# LCmeter0-LCD-8pinlcd-PIC_COMP.net
KiCad netlist of a schematic drawn in EAGLE
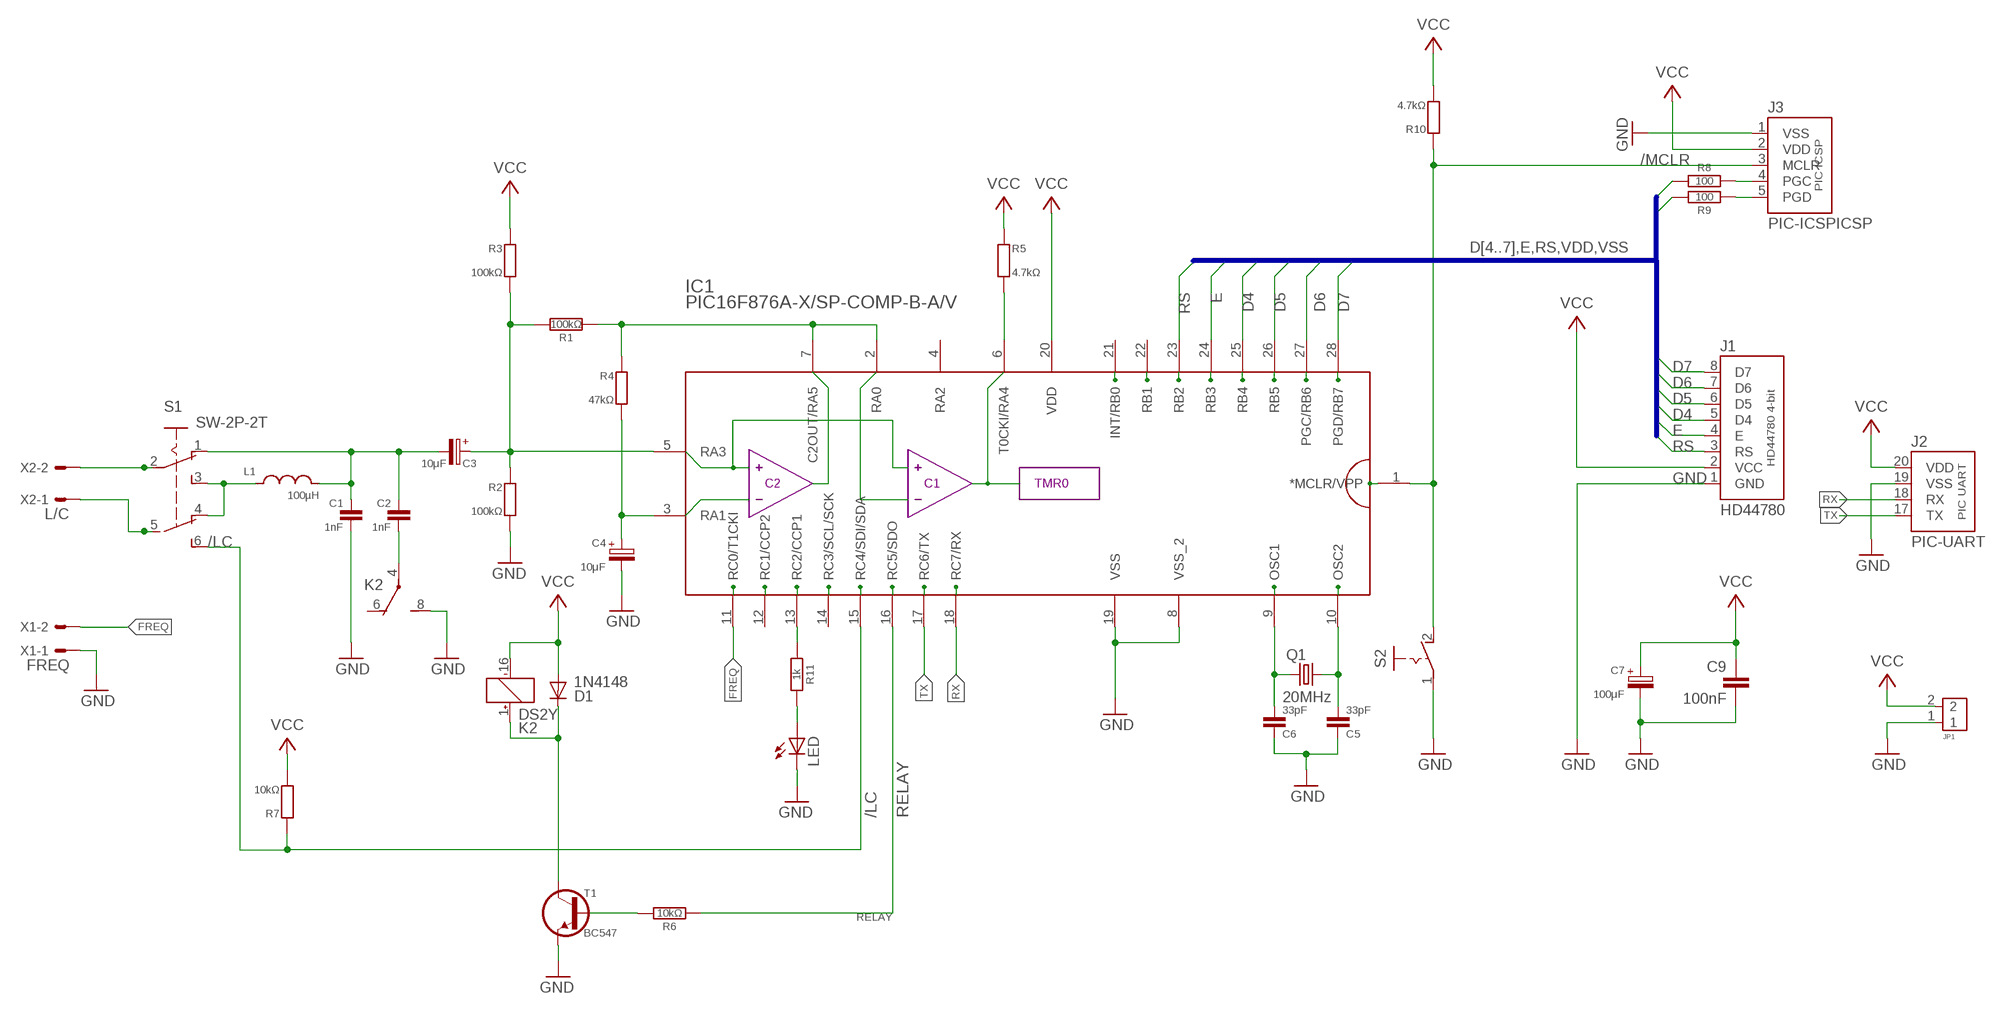
[diagram p0: schematic, sheet 1]

(export (version "E")
  (design (tool "Eeschema 10.0.6"))
  (components
    (comp (ref "C1")
      (value "1nF")
      (footprint "eagle-import:C050-020X036")
      (libsource (lib "eagle-import") (part "C050-020X036"))
    )
    (comp (ref "C2")
      (value "1nF")
      (footprint "eagle-import:C050-020X036")
      (libsource (lib "eagle-import") (part "C050-020X036"))
    )
    (comp (ref "C3")
      (value "10μF")
      (footprint "eagle-import:E2,5-4")
      (libsource (lib "eagle-import") (part "CPOL-HE2,5-4"))
    )
    (comp (ref "C4")
      (value "10μF")
      (footprint "eagle-import:E2,5-4")
      (libsource (lib "eagle-import") (part "CPOLE2,5-4"))
    )
    (comp (ref "C5")
      (value "33pF")
      (footprint "eagle-import:C025-020X036")
      (libsource (lib "eagle-import") (part "C025-020X036"))
    )
    (comp (ref "C6")
      (value "33pF")
      (footprint "eagle-import:C025-020X036")
      (libsource (lib "eagle-import") (part "C025-020X036"))
    )
    (comp (ref "C7")
      (value "100μF")
      (footprint "eagle-import:E2,5-5")
      (libsource (lib "eagle-import") (part "CPOLE2.5-5"))
    )
    (comp (ref "C9")
      (value "100nF")
      (footprint "eagle-import:C025-024X044")
      (libsource (lib "eagle-import") (part "C-EU025-024X044"))
    )
    (comp (ref "D1")
      (value "1N4148")
      (footprint "eagle-import:DO34-7")
      (libsource (lib "eagle-import") (part "1N414834-7"))
    )
    (comp (ref "IC1")
      (value "PIC16F876A-X/SP-COMP-B-A/V")
      (footprint "eagle-import:DIL28-3_V")
      (libsource (lib "eagle-import") (part "PIC16F876A-X/SP-COMP-B-A/V"))
    )
    (comp (ref "J1")
      (value "HD44780")
      (footprint "eagle-import:CONN-8P")
      (libsource (lib "eagle-import") (part "HD44780-4BIT-8PIN"))
    )
    (comp (ref "J2")
      (value "PIC-UART")
      (footprint "eagle-import:PIC-UART")
      (libsource (lib "eagle-import") (part "PIC-UART"))
    )
    (comp (ref "J3")
      (value "PIC-ICSPICSP")
      (footprint "eagle-import:PIC-ICSP")
      (libsource (lib "eagle-import") (part "PIC-ICSPICSP"))
    )
    (comp (ref "JP1")
      (value "CONN-2P2P/V")
      (footprint "eagle-import:CONN-2P-V")
      (libsource (lib "eagle-import") (part "CONN-2P2P/V"))
    )
    (comp (ref "K2")
      (value "DS2Y")
      (footprint "eagle-import:DS2Y")
      (fields (field (name "MPN") "DS2Y-S-DC5V"))
      (libsource (lib "eagle-import") (part "DS2Y-S-DC5V"))
    )
    (comp (ref "L1")
      (value "100µH")
      (footprint "eagle-import:L-02_5V")
      (libsource (lib "eagle-import") (part "L-SHORT02/5"))
    )
    (comp (ref "LED")
      (value "TLLG4400")
      (footprint "eagle-import:LED3MM")
      (fields (field (name "MF") "VISHAY SEMICONDUCTOR"))
      (libsource (lib "eagle-import") (part "TLLG4400"))
    )
    (comp (ref "Q1")
      (value "20MHz")
      (footprint "eagle-import:HC49")
      (libsource (lib "eagle-import") (part "CRYSTALHC49"))
    )
    (comp (ref "R1")
      (value "100kΩ")
      (footprint "eagle-import:0202_7")
      (libsource (lib "eagle-import") (part "R-H0202/7"))
    )
    (comp (ref "R2")
      (value "100kΩ")
      (footprint "eagle-import:0202_7")
      (libsource (lib "eagle-import") (part "R0202/7"))
    )
    (comp (ref "R3")
      (value "100kΩ")
      (footprint "eagle-import:0202_7")
      (libsource (lib "eagle-import") (part "R0202/7"))
    )
    (comp (ref "R4")
      (value "47kΩ")
      (footprint "eagle-import:0202_7")
      (libsource (lib "eagle-import") (part "R0202/7"))
    )
    (comp (ref "R5")
      (value "4.7kΩ")
      (footprint "eagle-import:0202_7")
      (libsource (lib "eagle-import") (part "R0202/7"))
    )
    (comp (ref "R6")
      (value "10kΩ")
      (footprint "eagle-import:0202_7")
      (libsource (lib "eagle-import") (part "R-H0202/7"))
    )
    (comp (ref "R7")
      (value "10kΩ")
      (footprint "eagle-import:0202_10")
      (libsource (lib "eagle-import") (part "R0202/10"))
    )
    (comp (ref "R8")
      (value "100")
      (footprint "eagle-import:0202_5")
      (libsource (lib "eagle-import") (part "R-H0202/5"))
    )
    (comp (ref "R9")
      (value "100")
      (footprint "eagle-import:0202_5")
      (libsource (lib "eagle-import") (part "R-H0202/5"))
    )
    (comp (ref "R10")
      (value "4.7kΩ")
      (footprint "eagle-import:0202_7")
      (libsource (lib "eagle-import") (part "R0202/7"))
    )
    (comp (ref "R11")
      (value "1k")
      (footprint "eagle-import:0202_5")
      (libsource (lib "eagle-import") (part "R-H0202/5"))
    )
    (comp (ref "S1")
      (value "SW-2P-2T")
      (footprint "eagle-import:SLSW-2P2T")
      (libsource (lib "eagle-import") (part "SW-2P-2T"))
    )
    (comp (ref "S2")
      (value "PB-1P-1T")
      (footprint "eagle-import:PB-1P1T")
      (libsource (lib "eagle-import") (part "PB-1P-1T"))
    )
    (comp (ref "T1")
      (value "BC547")
      (footprint "eagle-import:TO92-CBE-A")
      (libsource (lib "eagle-import") (part "BC547CBE-A"))
    )
    (comp (ref "X1")
      (value "FREQ")
      (footprint "eagle-import:70543-02")
      (libsource (lib "eagle-import") (part "C-GRID-02-70543"))
    )
    (comp (ref "X2")
      (value "L/C")
      (footprint "eagle-import:70543-02")
      (libsource (lib "eagle-import") (part "C-GRID-02-70543"))
    )
  )
  (nets
    (net (code "3") (name "/D4") (class "Default")
      (node (ref "IC1") (pin "25") (pinfunction "RB4_25") (pintype "passive"))
      (node (ref "J1") (pin "5") (pinfunction "D4_5") (pintype "passive"))
    )
    (net (code "4") (name "/D5") (class "Default")
      (node (ref "IC1") (pin "26") (pinfunction "RB5_26") (pintype "passive"))
      (node (ref "J1") (pin "6") (pinfunction "D5_6") (pintype "passive"))
    )
    (net (code "5") (name "/D6") (class "Default")
      (node (ref "IC1") (pin "27") (pinfunction "PGC/RB6_27") (pintype "passive"))
      (node (ref "J1") (pin "7") (pinfunction "D6_7") (pintype "passive"))
      (node (ref "R9") (pin "1") (pinfunction "1_1") (pintype "passive"))
    )
    (net (code "6") (name "/D7") (class "Default")
      (node (ref "IC1") (pin "28") (pinfunction "PGD/RB7_28") (pintype "passive"))
      (node (ref "J1") (pin "8") (pinfunction "D7_8") (pintype "passive"))
      (node (ref "R8") (pin "1") (pinfunction "1_1") (pintype "passive"))
    )
    (net (code "7") (name "/E") (class "Default")
      (node (ref "IC1") (pin "24") (pinfunction "RB3_24") (pintype "passive"))
      (node (ref "J1") (pin "4") (pinfunction "E_4") (pintype "passive"))
    )
    (net (code "8") (name "/RELAY") (class "Default")
      (node (ref "IC1") (pin "16") (pinfunction "RC5/SDO_16") (pintype "passive"))
      (node (ref "R6") (pin "2") (pinfunction "2_2") (pintype "passive"))
    )
    (net (code "9") (name "/RS") (class "Default")
      (node (ref "IC1") (pin "23") (pinfunction "RB2_23") (pintype "passive"))
      (node (ref "J1") (pin "3") (pinfunction "RS_3") (pintype "passive"))
    )
    (net (code "11") (name "/{slash}LC") (class "Default")
      (node (ref "IC1") (pin "15") (pinfunction "RC4/SDI/SDA_15") (pintype "passive"))
      (node (ref "R7") (pin "1") (pinfunction "1_1") (pintype "passive"))
      (node (ref "S1") (pin "6") (pinfunction "S1_6") (pintype "passive"))
    )
    (net (code "12") (name "/{slash}MCLR") (class "Default")
      (node (ref "IC1") (pin "1") (pinfunction "*MCLR/VPP_1") (pintype "passive"))
      (node (ref "J3") (pin "3") (pinfunction "MCLR_3") (pintype "passive"))
      (node (ref "R10") (pin "1") (pinfunction "1_1") (pintype "passive"))
      (node (ref "S2") (pin "2") (pinfunction "S_2") (pintype "passive"))
    )
    (net (code "13") (name "FREQ") (class "Default")
      (node (ref "IC1") (pin "11") (pinfunction "RC0/T1CKI_11") (pintype "passive"))
      (node (ref "X1") (pin "2") (pinfunction "S_2") (pintype "passive"))
    )
    (net (code "14") (name "GND") (class "Default")
      (node (ref "C1") (pin "2") (pinfunction "2_2") (pintype "passive"))
      (node (ref "C4") (pin "-") (pinfunction "-_-") (pintype "passive"))
      (node (ref "C5") (pin "1") (pinfunction "1_1") (pintype "passive"))
      (node (ref "C6") (pin "1") (pinfunction "1_1") (pintype "passive"))
      (node (ref "C7") (pin "-") (pinfunction "-_-") (pintype "passive"))
      (node (ref "C9") (pin "2") (pinfunction "2_2") (pintype "passive"))
      (node (ref "IC1") (pin "19") (pinfunction "VSS_19") (pintype "passive"))
      (node (ref "IC1") (pin "8") (pinfunction "VSS_2_8") (pintype "passive"))
      (node (ref "J1") (pin "1") (pinfunction "GND_1") (pintype "passive"))
      (node (ref "J2") (pin "19") (pinfunction "VSS_19") (pintype "passive"))
      (node (ref "J3") (pin "1") (pinfunction "VSS_1") (pintype "passive"))
      (node (ref "JP1") (pin "1") (pinfunction "1_1") (pintype "bidirectional"))
      (node (ref "K2") (pin "8") (pinfunction "S_8") (pintype "passive"))
      (node (ref "LED") (pin "K") (pinfunction "C_K") (pintype "passive"))
      (node (ref "R2") (pin "2") (pinfunction "2_2") (pintype "passive"))
      (node (ref "S2") (pin "1") (pinfunction "P_1") (pintype "passive"))
      (node (ref "T1") (pin "E") (pinfunction "E_E") (pintype "passive"))
      (node (ref "X1") (pin "1") (pinfunction "S_1") (pintype "passive"))
    )
    (net (code "15") (name "Net-(IC1-C2OUT{slash}RA5)") (class "Default")
      (node (ref "IC1") (pin "2") (pinfunction "RA0_2") (pintype "passive"))
      (node (ref "IC1") (pin "7") (pinfunction "C2OUT/RA5_7") (pintype "passive"))
      (node (ref "R1") (pin "1") (pinfunction "1_1") (pintype "passive"))
      (node (ref "R4") (pin "1") (pinfunction "1_1") (pintype "passive"))
    )
    (net (code "16") (name "Net-(IC1-OSC1)") (class "Default")
      (node (ref "C6") (pin "2") (pinfunction "2_2") (pintype "passive"))
      (node (ref "IC1") (pin "9") (pinfunction "OSC1_9") (pintype "passive"))
      (node (ref "Q1") (pin "1") (pinfunction "1_1") (pintype "passive"))
    )
    (net (code "17") (name "Net-(IC1-OSC2)") (class "Default")
      (node (ref "C5") (pin "2") (pinfunction "2_2") (pintype "passive"))
      (node (ref "IC1") (pin "10") (pinfunction "OSC2_10") (pintype "passive"))
      (node (ref "Q1") (pin "2") (pinfunction "2_2") (pintype "passive"))
    )
    (net (code "18") (name "Net-(IC1-RA1)") (class "Default")
      (node (ref "C4") (pin "+") (pinfunction "+_+") (pintype "passive"))
      (node (ref "IC1") (pin "3") (pinfunction "RA1_3") (pintype "passive"))
      (node (ref "R4") (pin "2") (pinfunction "2_2") (pintype "passive"))
    )
    (net (code "19") (name "Net-(IC1-RA3)") (class "Default")
      (node (ref "C3") (pin "+") (pinfunction "+_+") (pintype "passive"))
      (node (ref "IC1") (pin "5") (pinfunction "RA3_5") (pintype "passive"))
      (node (ref "R1") (pin "2") (pinfunction "2_2") (pintype "passive"))
      (node (ref "R2") (pin "1") (pinfunction "1_1") (pintype "passive"))
      (node (ref "R3") (pin "2") (pinfunction "2_2") (pintype "passive"))
    )
    (net (code "20") (name "Net-(IC1-RC2{slash}CCP1)") (class "Default")
      (node (ref "IC1") (pin "13") (pinfunction "RC2/CCP1_13") (pintype "passive"))
      (node (ref "R11") (pin "2") (pinfunction "2_2") (pintype "passive"))
    )
    (net (code "21") (name "Net-(IC1-T0CKI{slash}RA4)") (class "Default")
      (node (ref "IC1") (pin "6") (pinfunction "T0CKI/RA4_6") (pintype "passive"))
      (node (ref "R5") (pin "2") (pinfunction "2_2") (pintype "passive"))
    )
    (net (code "22") (name "Net-(J3-PGC)") (class "Default")
      (node (ref "J3") (pin "4") (pinfunction "PGC_4") (pintype "passive"))
      (node (ref "R8") (pin "2") (pinfunction "2_2") (pintype "passive"))
    )
    (net (code "23") (name "Net-(J3-PGD)") (class "Default")
      (node (ref "J3") (pin "5") (pinfunction "PGD_5") (pintype "passive"))
      (node (ref "R9") (pin "2") (pinfunction "2_2") (pintype "passive"))
    )
    (net (code "24") (name "Net-(K2A-+)") (class "Default")
      (node (ref "D1") (pin "C") (pinfunction "C_C") (pintype "passive"))
      (node (ref "K2") (pin "1") (pinfunction "+_1") (pintype "passive"))
      (node (ref "T1") (pin "C") (pinfunction "C_C") (pintype "passive"))
    )
    (net (code "25") (name "Net-(K2B-P)") (class "Default")
      (node (ref "C2") (pin "2") (pinfunction "2_2") (pintype "passive"))
      (node (ref "K2") (pin "4") (pinfunction "P_4") (pintype "passive"))
    )
    (net (code "26") (name "Net-(LED-PadA)") (class "Default")
      (node (ref "LED") (pin "A") (pinfunction "A_A") (pintype "passive"))
      (node (ref "R11") (pin "1") (pinfunction "1_1") (pintype "passive"))
    )
    (net (code "27") (name "Net-(R6-Pad1)") (class "Default")
      (node (ref "R6") (pin "1") (pinfunction "1_1") (pintype "passive"))
      (node (ref "T1") (pin "B") (pinfunction "B_B") (pintype "passive"))
    )
    (net (code "28") (name "Net-(S1-O)") (class "Default")
      (node (ref "C1") (pin "1") (pinfunction "1_1") (pintype "passive"))
      (node (ref "C2") (pin "1") (pinfunction "1_1") (pintype "passive"))
      (node (ref "C3") (pin "-") (pinfunction "-_-") (pintype "passive"))
      (node (ref "L1") (pin "2") (pinfunction "2_2") (pintype "passive"))
      (node (ref "S1") (pin "1") (pinfunction "O_1") (pintype "passive"))
    )
    (net (code "29") (name "Net-(S1-O1)") (class "Default")
      (node (ref "L1") (pin "1") (pinfunction "1_1") (pintype "passive"))
      (node (ref "S1") (pin "3") (pinfunction "S_3") (pintype "passive"))
      (node (ref "S1") (pin "4") (pinfunction "O1_4") (pintype "passive"))
    )
    (net (code "30") (name "Net-(S1-P)") (class "Default")
      (node (ref "S1") (pin "2") (pinfunction "P_2") (pintype "passive"))
      (node (ref "X2") (pin "2") (pinfunction "S_2") (pintype "passive"))
    )
    (net (code "31") (name "Net-(S1-P1)") (class "Default")
      (node (ref "S1") (pin "5") (pinfunction "P1_5") (pintype "passive"))
      (node (ref "X2") (pin "1") (pinfunction "S_1") (pintype "passive"))
    )
    (net (code "32") (name "RX") (class "Default")
      (node (ref "IC1") (pin "18") (pinfunction "RC7/RX_18") (pintype "passive"))
      (node (ref "J2") (pin "18") (pinfunction "RX_18") (pintype "passive"))
    )
    (net (code "33") (name "TX") (class "Default")
      (node (ref "IC1") (pin "17") (pinfunction "RC6/TX_17") (pintype "passive"))
      (node (ref "J2") (pin "17") (pinfunction "TX_17") (pintype "passive"))
    )
    (net (code "34") (name "VCC") (class "Default")
      (node (ref "C7") (pin "+") (pinfunction "+_+") (pintype "passive"))
      (node (ref "C9") (pin "1") (pinfunction "1_1") (pintype "passive"))
      (node (ref "D1") (pin "A") (pinfunction "A_A") (pintype "passive"))
      (node (ref "IC1") (pin "20") (pinfunction "VDD_20") (pintype "passive"))
      (node (ref "J1") (pin "2") (pinfunction "VCC_2") (pintype "passive"))
      (node (ref "J2") (pin "20") (pinfunction "VDD_20") (pintype "passive"))
      (node (ref "J3") (pin "2") (pinfunction "VDD_2") (pintype "passive"))
      (node (ref "JP1") (pin "2") (pinfunction "2_2") (pintype "bidirectional"))
      (node (ref "K2") (pin "16") (pinfunction "-_16") (pintype "passive"))
      (node (ref "R10") (pin "2") (pinfunction "2_2") (pintype "passive"))
      (node (ref "R3") (pin "1") (pinfunction "1_1") (pintype "passive"))
      (node (ref "R5") (pin "1") (pinfunction "1_1") (pintype "passive"))
      (node (ref "R7") (pin "2") (pinfunction "2_2") (pintype "passive"))
    )
    (net (code "35") (name "unconnected-(IC1-INT{slash}RB0-Pad21)") (class "Default")
      (node (ref "IC1") (pin "21") (pinfunction "INT/RB0_21") (pintype "passive"))
    )
    (net (code "36") (name "unconnected-(IC1-RA2-Pad4)") (class "Default")
      (node (ref "IC1") (pin "4") (pinfunction "RA2_4") (pintype "passive"))
    )
    (net (code "37") (name "unconnected-(IC1-RB1-Pad22)") (class "Default")
      (node (ref "IC1") (pin "22") (pinfunction "RB1_22") (pintype "passive"))
    )
    (net (code "38") (name "unconnected-(IC1-RC1{slash}CCP2-Pad12)") (class "Default")
      (node (ref "IC1") (pin "12") (pinfunction "RC1/CCP2_12") (pintype "passive"))
    )
    (net (code "39") (name "unconnected-(IC1-RC3{slash}SCL{slash}SCK-Pad14)") (class "Default")
      (node (ref "IC1") (pin "14") (pinfunction "RC3/SCL/SCK_14") (pintype "passive"))
    )
    (net (code "40") (name "unconnected-(K2B-O-Pad6)") (class "Default")
      (node (ref "K2") (pin "6") (pinfunction "O_6") (pintype "passive"))
    )
  )
)
